# power-bridge.net
KiCad netlist of a schematic drawn in EAGLE
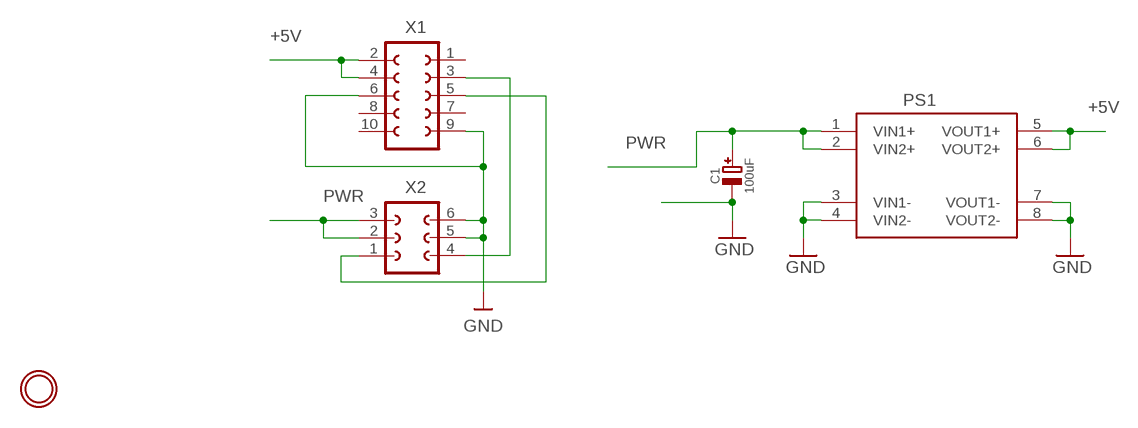
[diagram p0: schematic, sheet 1]

(export (version "E")
  (design (tool "Eeschema 10.0.6"))
  (components
    (comp (ref "C1")
      (value "100uF")
      (footprint "eagle-import:CELEC_3.5MM_8MM")
      (libsource (lib "eagle-import") (part "CAP_ELECTROLYTICPTH_3.5MMGRID_8MMDIA"))
    )
    (comp (ref "PS1")
      (value "K8801MODULE")
      (footprint "eagle-import:K8801")
      (libsource (lib "eagle-import") (part "K8801MODULE"))
    )
    (comp (ref "U$2")
      (value "MOUNTINGHOLE2.7_THICK")
      (footprint "eagle-import:MOUNTINGHOLE_2.7_PLATED_THICK")
      (libsource (lib "eagle-import") (part "MOUNTINGHOLE2.7_THICK"))
    )
    (comp (ref "X1")
      (value "CON-FE05-2")
      (footprint "eagle-import:FE05-2")
      (libsource (lib "eagle-import") (part "CON-FE05-2"))
    )
    (comp (ref "X2")
      (value "CON-MA03-2PCB_EDGE")
      (footprint "eagle-import:PCB_EDGE_03-2")
      (libsource (lib "eagle-import") (part "CON-MA03-2PCB_EDGE"))
    )
  )
  (nets
    (net (code "1") (name "/+5V") (class "Default")
      (node (ref "PS1") (pin "5") (pinfunction "VOUT1+_5") (pintype "bidirectional"))
      (node (ref "PS1") (pin "6") (pinfunction "VOUT2+_6") (pintype "bidirectional"))
      (node (ref "X1") (pin "2") (pinfunction "2_2") (pintype "passive"))
      (node (ref "X1") (pin "4") (pinfunction "4_4") (pintype "passive"))
    )
    (net (code "2") (name "/PWR") (class "Default")
      (node (ref "C1") (pin "+") (pinfunction "+_+") (pintype "passive"))
      (node (ref "PS1") (pin "1") (pinfunction "VIN1+_1") (pintype "bidirectional"))
      (node (ref "PS1") (pin "2") (pinfunction "VIN2+_2") (pintype "bidirectional"))
      (node (ref "X2") (pin "2") (pinfunction "2_2") (pintype "passive"))
      (node (ref "X2") (pin "3") (pinfunction "3_3") (pintype "passive"))
    )
    (net (code "3") (name "GND") (class "Default")
      (node (ref "C1") (pin "-") (pinfunction "-_-") (pintype "passive"))
      (node (ref "PS1") (pin "3") (pinfunction "VIN1-_3") (pintype "bidirectional"))
      (node (ref "PS1") (pin "4") (pinfunction "VIN2-_4") (pintype "bidirectional"))
      (node (ref "PS1") (pin "7") (pinfunction "VOUT1-_7") (pintype "bidirectional"))
      (node (ref "PS1") (pin "8") (pinfunction "VOUT2-_8") (pintype "bidirectional"))
      (node (ref "X1") (pin "6") (pinfunction "6_6") (pintype "passive"))
      (node (ref "X1") (pin "9") (pinfunction "9_9") (pintype "passive"))
      (node (ref "X2") (pin "5") (pinfunction "5_5") (pintype "passive"))
      (node (ref "X2") (pin "6") (pinfunction "6_6") (pintype "passive"))
    )
    (net (code "4") (name "Net-(X1-Pad3)") (class "Default")
      (node (ref "X1") (pin "3") (pinfunction "3_3") (pintype "passive"))
      (node (ref "X2") (pin "4") (pinfunction "4_4") (pintype "passive"))
    )
    (net (code "5") (name "Net-(X1-Pad5)") (class "Default")
      (node (ref "X1") (pin "5") (pinfunction "5_5") (pintype "passive"))
      (node (ref "X2") (pin "1") (pinfunction "1_1") (pintype "passive"))
    )
    (net (code "6") (name "unconnected-(X1-Pad1)") (class "Default")
      (node (ref "X1") (pin "1") (pinfunction "1_1") (pintype "passive"))
    )
    (net (code "7") (name "unconnected-(X1-Pad7)") (class "Default")
      (node (ref "X1") (pin "7") (pinfunction "7_7") (pintype "passive"))
    )
    (net (code "8") (name "unconnected-(X1-Pad8)") (class "Default")
      (node (ref "X1") (pin "8") (pinfunction "8_8") (pintype "passive"))
    )
    (net (code "9") (name "unconnected-(X1-Pad10)") (class "Default")
      (node (ref "X1") (pin "10") (pinfunction "10_10") (pintype "passive"))
    )
  )
)
